# adp5350-breakout.net
KiCad netlist of a schematic drawn in EAGLE
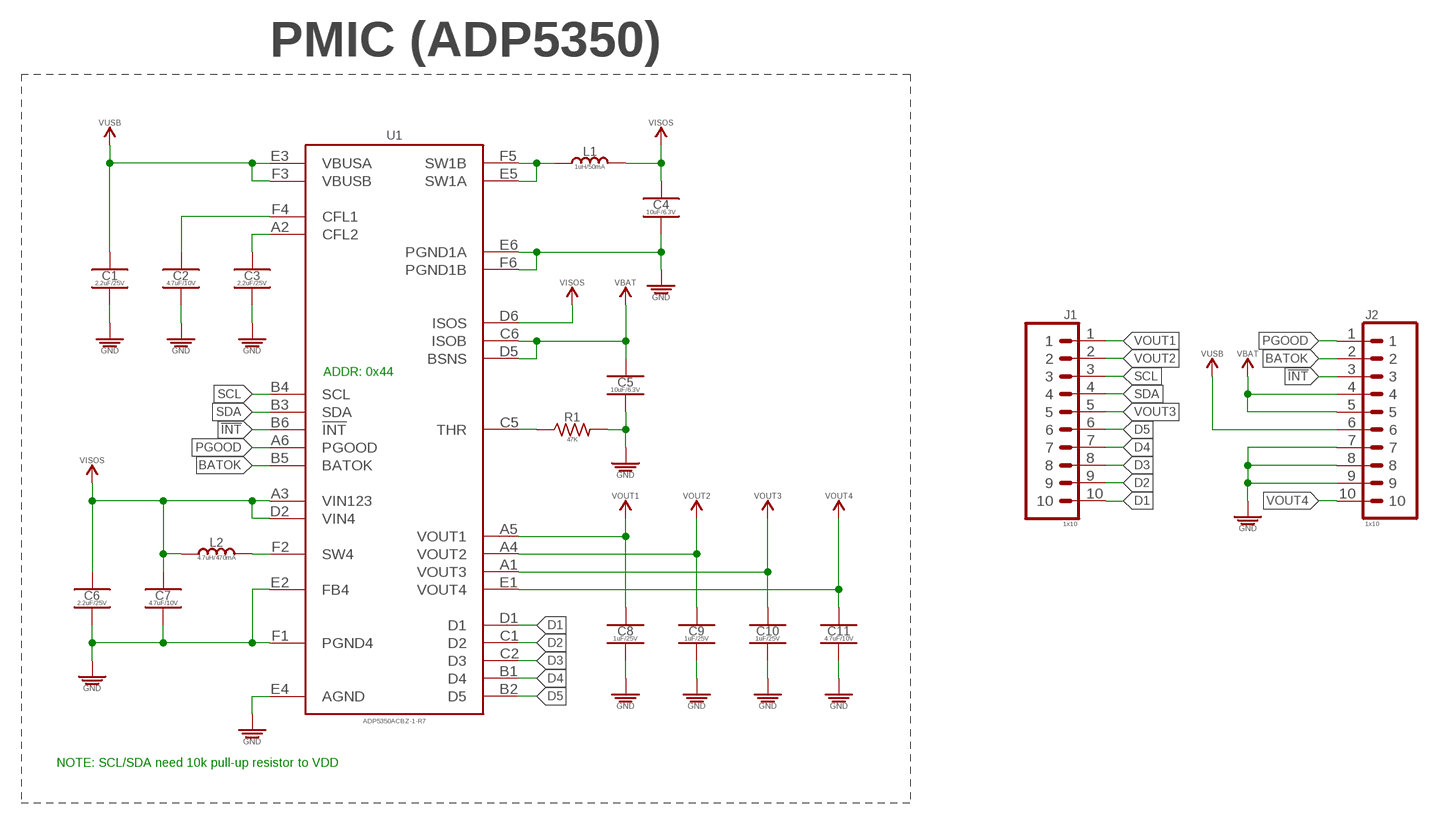
[diagram p0: schematic, sheet 1]

(export (version "E")
  (design (tool "Eeschema 10.0.6"))
  (components
    (comp (ref "C1")
      (value "2.2uF/25V")
      (footprint "eagle-import:CAPC1005X55_SMD-0402")
      (fields (field (name "MFR") "TDK Corporation") (field (name "MPN") "C1005X5R1E225K050BC"))
      (libsource (lib "eagle-import") (part "2.2UF_CER_SMD-0402_25V-10%"))
    )
    (comp (ref "C2")
      (value "4.7uF/10V")
      (footprint "eagle-import:CAPC1005X55_SMD-0402")
      (fields (field (name "MFR") "Samsung Electro-Mechanics") (field (name "MPN") "CL05A475MP5NRNC"))
      (libsource (lib "eagle-import") (part "4.7UF_CER_SMD-0402_10V-20%"))
    )
    (comp (ref "C3")
      (value "2.2uF/25V")
      (footprint "eagle-import:CAPC1005X55_SMD-0402")
      (fields (field (name "MFR") "TDK Corporation") (field (name "MPN") "C1005X5R1E225K050BC"))
      (libsource (lib "eagle-import") (part "2.2UF_CER_SMD-0402_25V-10%"))
    )
    (comp (ref "C4")
      (value "10uF/6.3V")
      (footprint "eagle-import:CAPC1005X55_SMD-0402")
      (fields
        (field (name "MFR") "Murata Electronics North America")
        (field (name "MPN") "GRM155C80J106ME11D")
      )
      (libsource (lib "eagle-import") (part "10UF_CER_SMD-0402_6.3V-20%"))
    )
    (comp (ref "C5")
      (value "10uF/6.3V")
      (footprint "eagle-import:CAPC1005X55_SMD-0402")
      (fields
        (field (name "MFR") "Murata Electronics North America")
        (field (name "MPN") "GRM155C80J106ME11D")
      )
      (libsource (lib "eagle-import") (part "10UF_CER_SMD-0402_6.3V-20%"))
    )
    (comp (ref "C6")
      (value "2.2uF/25V")
      (footprint "eagle-import:CAPC1005X55_SMD-0402")
      (fields (field (name "MFR") "TDK Corporation") (field (name "MPN") "C1005X5R1E225K050BC"))
      (libsource (lib "eagle-import") (part "2.2UF_CER_SMD-0402_25V-10%"))
    )
    (comp (ref "C7")
      (value "4.7uF/10V")
      (footprint "eagle-import:CAPC1005X55_SMD-0402")
      (fields (field (name "MFR") "Samsung Electro-Mechanics") (field (name "MPN") "CL05A475MP5NRNC"))
      (libsource (lib "eagle-import") (part "4.7UF_CER_SMD-0402_10V-20%"))
    )
    (comp (ref "C8")
      (value "1uF/25V")
      (footprint "eagle-import:CAPC1005X55_SMD-0402")
      (fields (field (name "MFR") "TDK Corporation") (field (name "MPN") "CGB2A1X5R1E105K033BC"))
      (libsource (lib "eagle-import") (part "1UF_CER_SMD-0402_25V-10%"))
    )
    (comp (ref "C9")
      (value "1uF/25V")
      (footprint "eagle-import:CAPC1005X55_SMD-0402")
      (fields (field (name "MFR") "TDK Corporation") (field (name "MPN") "CGB2A1X5R1E105K033BC"))
      (libsource (lib "eagle-import") (part "1UF_CER_SMD-0402_25V-10%"))
    )
    (comp (ref "C10")
      (value "1uF/25V")
      (footprint "eagle-import:CAPC1005X55_SMD-0402")
      (fields (field (name "MFR") "TDK Corporation") (field (name "MPN") "CGB2A1X5R1E105K033BC"))
      (libsource (lib "eagle-import") (part "1UF_CER_SMD-0402_25V-10%"))
    )
    (comp (ref "C11")
      (value "4.7uF/10V")
      (footprint "eagle-import:CAPC1005X55_SMD-0402")
      (fields (field (name "MFR") "Samsung Electro-Mechanics") (field (name "MPN") "CL05A475MP5NRNC"))
      (libsource (lib "eagle-import") (part "4.7UF_CER_SMD-0402_10V-20%"))
    )
    (comp (ref "J1")
      (value "1x10")
      (footprint "eagle-import:HDRV10W64P254_1X10_2540X254X838B")
      (fields (field (name "MFR") "Sullins Connector Solutions") (field (name "MPN") "PEC10SAAN"))
      (libsource (lib "eagle-import") (part "1X10_PTH_VERT-MALE_2.54MM"))
    )
    (comp (ref "J2")
      (value "1x10")
      (footprint "eagle-import:HDRV10W64P254_1X10_2540X254X838B")
      (fields (field (name "MFR") "Sullins Connector Solutions") (field (name "MPN") "PEC10SAAN"))
      (libsource (lib "eagle-import") (part "1X10_PTH_VERT-MALE_2.54MM"))
    )
    (comp (ref "L1")
      (value "1uH/50mA")
      (footprint "eagle-import:INDC1608X60-0603")
      (fields (field (name "MFR") "TDK Corporation") (field (name "MPN") "MLF1608A1R5KTA00"))
      (libsource (lib "eagle-import") (part "1UH_SMD-0603_0.50A-0.700OHM-10%"))
    )
    (comp (ref "L2")
      (value "4.7uH/470mA")
      (footprint "eagle-import:INDC1608X60-0603")
      (fields (field (name "MFR") "Taiyo Yuden") (field (name "MPN") "CBMF1608T4R7M"))
      (libsource (lib "eagle-import") (part "4.7UH_SMD-0603_470MA-0.312OHM-20%"))
    )
    (comp (ref "R1")
      (value "47K")
      (footprint "eagle-import:RESC1005X35_SMD-0402")
      (fields (field (name "MFR") "Yageo") (field (name "MPN") "AC0402JR-0747KL"))
      (libsource (lib "eagle-import") (part "47KΩ_SMD-0402_1/16W-5%"))
    )
    (comp (ref "U1")
      (value "ADP5350ACBZ-1-R7")
      (footprint "eagle-import:BGA36C50P6X6_331X336X66N")
      (fields (field (name "MFR") "Analog Devices Inc."))
      (libsource (lib "eagle-import") (part "ADP5350ACBZ-1-R7"))
    )
  )
  (nets
    (net (code "1") (name "/~{INT}") (class "Default")
      (node (ref "J2") (pin "3") (pinfunction "3_3") (pintype "passive"))
      (node (ref "U1") (pin "B6") (pinfunction "~{INT}_B6") (pintype "bidirectional"))
    )
    (net (code "2") (name "BATOK") (class "Default")
      (node (ref "J2") (pin "2") (pinfunction "2_2") (pintype "passive"))
      (node (ref "U1") (pin "B5") (pinfunction "BATOK_B5") (pintype "bidirectional"))
    )
    (net (code "3") (name "D1") (class "Default")
      (node (ref "J1") (pin "10") (pinfunction "10_10") (pintype "passive"))
      (node (ref "U1") (pin "D1") (pinfunction "D1_D1") (pintype "bidirectional"))
    )
    (net (code "4") (name "D2") (class "Default")
      (node (ref "J1") (pin "9") (pinfunction "9_9") (pintype "passive"))
      (node (ref "U1") (pin "C1") (pinfunction "D2_C1") (pintype "bidirectional"))
    )
    (net (code "5") (name "D3") (class "Default")
      (node (ref "J1") (pin "8") (pinfunction "8_8") (pintype "passive"))
      (node (ref "U1") (pin "C2") (pinfunction "D3_C2") (pintype "bidirectional"))
    )
    (net (code "6") (name "D4") (class "Default")
      (node (ref "J1") (pin "7") (pinfunction "7_7") (pintype "passive"))
      (node (ref "U1") (pin "B1") (pinfunction "D4_B1") (pintype "bidirectional"))
    )
    (net (code "7") (name "D5") (class "Default")
      (node (ref "J1") (pin "6") (pinfunction "6_6") (pintype "passive"))
      (node (ref "U1") (pin "B2") (pinfunction "D5_B2") (pintype "bidirectional"))
    )
    (net (code "8") (name "GND") (class "Default")
      (node (ref "C1") (pin "2") (pinfunction "2_2") (pintype "passive"))
      (node (ref "C10") (pin "2") (pinfunction "2_2") (pintype "passive"))
      (node (ref "C11") (pin "2") (pinfunction "2_2") (pintype "passive"))
      (node (ref "C2") (pin "2") (pinfunction "2_2") (pintype "passive"))
      (node (ref "C3") (pin "2") (pinfunction "2_2") (pintype "passive"))
      (node (ref "C4") (pin "2") (pinfunction "2_2") (pintype "passive"))
      (node (ref "C5") (pin "2") (pinfunction "2_2") (pintype "passive"))
      (node (ref "C6") (pin "2") (pinfunction "2_2") (pintype "passive"))
      (node (ref "C7") (pin "2") (pinfunction "2_2") (pintype "passive"))
      (node (ref "C8") (pin "2") (pinfunction "2_2") (pintype "passive"))
      (node (ref "C9") (pin "2") (pinfunction "2_2") (pintype "passive"))
      (node (ref "J2") (pin "7") (pinfunction "7_7") (pintype "passive"))
      (node (ref "J2") (pin "8") (pinfunction "8_8") (pintype "passive"))
      (node (ref "J2") (pin "9") (pinfunction "9_9") (pintype "passive"))
      (node (ref "R1") (pin "2") (pinfunction "2_2") (pintype "passive"))
      (node (ref "U1") (pin "E2") (pinfunction "FB4_E2") (pintype "bidirectional"))
      (node (ref "U1") (pin "E4") (pinfunction "AGND_E4") (pintype "power_in"))
      (node (ref "U1") (pin "E6") (pinfunction "PGND1A_E6") (pintype "power_in"))
      (node (ref "U1") (pin "F1") (pinfunction "PGND4_F1") (pintype "power_in"))
      (node (ref "U1") (pin "F6") (pinfunction "PGND1B_F6") (pintype "power_in"))
    )
    (net (code "9") (name "Net-(U1-CFL1)") (class "Default")
      (node (ref "C2") (pin "1") (pinfunction "1_1") (pintype "passive"))
      (node (ref "U1") (pin "F4") (pinfunction "CFL1_F4") (pintype "bidirectional"))
    )
    (net (code "10") (name "Net-(U1-CFL2)") (class "Default")
      (node (ref "C3") (pin "1") (pinfunction "1_1") (pintype "passive"))
      (node (ref "U1") (pin "A2") (pinfunction "CFL2_A2") (pintype "bidirectional"))
    )
    (net (code "11") (name "Net-(U1-SW1A)") (class "Default")
      (node (ref "L1") (pin "1") (pinfunction "1_1") (pintype "passive"))
      (node (ref "U1") (pin "E5") (pinfunction "SW1A_E5") (pintype "bidirectional"))
      (node (ref "U1") (pin "F5") (pinfunction "SW1B_F5") (pintype "bidirectional"))
    )
    (net (code "12") (name "Net-(U1-SW4)") (class "Default")
      (node (ref "L2") (pin "2") (pinfunction "2_2") (pintype "passive"))
      (node (ref "U1") (pin "F2") (pinfunction "SW4_F2") (pintype "bidirectional"))
    )
    (net (code "13") (name "Net-(U1-THR)") (class "Default")
      (node (ref "R1") (pin "1") (pinfunction "1_1") (pintype "passive"))
      (node (ref "U1") (pin "C5") (pinfunction "THR_C5") (pintype "bidirectional"))
    )
    (net (code "14") (name "PGOOD") (class "Default")
      (node (ref "J2") (pin "1") (pinfunction "1_1") (pintype "passive"))
      (node (ref "U1") (pin "A6") (pinfunction "PGOOD_A6") (pintype "bidirectional"))
    )
    (net (code "15") (name "SCL") (class "Default")
      (node (ref "J1") (pin "3") (pinfunction "3_3") (pintype "passive"))
      (node (ref "U1") (pin "B4") (pinfunction "SCL_B4") (pintype "bidirectional"))
    )
    (net (code "16") (name "SDA") (class "Default")
      (node (ref "J1") (pin "4") (pinfunction "4_4") (pintype "passive"))
      (node (ref "U1") (pin "B3") (pinfunction "SDA_B3") (pintype "bidirectional"))
    )
    (net (code "17") (name "VBAT") (class "Default")
      (node (ref "C5") (pin "1") (pinfunction "1_1") (pintype "passive"))
      (node (ref "J2") (pin "4") (pinfunction "4_4") (pintype "passive"))
      (node (ref "J2") (pin "5") (pinfunction "5_5") (pintype "passive"))
      (node (ref "U1") (pin "C6") (pinfunction "ISOB_C6") (pintype "bidirectional"))
      (node (ref "U1") (pin "D5") (pinfunction "BSNS_D5") (pintype "bidirectional"))
    )
    (net (code "18") (name "VISOS") (class "Default")
      (node (ref "C4") (pin "1") (pinfunction "1_1") (pintype "passive"))
      (node (ref "C6") (pin "1") (pinfunction "1_1") (pintype "passive"))
      (node (ref "C7") (pin "1") (pinfunction "1_1") (pintype "passive"))
      (node (ref "L1") (pin "2") (pinfunction "2_2") (pintype "passive"))
      (node (ref "L2") (pin "1") (pinfunction "1_1") (pintype "passive"))
      (node (ref "U1") (pin "A3") (pinfunction "VIN123_A3") (pintype "power_in"))
      (node (ref "U1") (pin "D2") (pinfunction "VIN4_D2") (pintype "power_in"))
      (node (ref "U1") (pin "D6") (pinfunction "ISOS_D6") (pintype "bidirectional"))
    )
    (net (code "19") (name "VOUT1") (class "Default")
      (node (ref "C8") (pin "1") (pinfunction "1_1") (pintype "passive"))
      (node (ref "J1") (pin "1") (pinfunction "1_1") (pintype "passive"))
      (node (ref "U1") (pin "A5") (pinfunction "VOUT1_A5") (pintype "power_in"))
    )
    (net (code "20") (name "VOUT2") (class "Default")
      (node (ref "C9") (pin "1") (pinfunction "1_1") (pintype "passive"))
      (node (ref "J1") (pin "2") (pinfunction "2_2") (pintype "passive"))
      (node (ref "U1") (pin "A4") (pinfunction "VOUT2_A4") (pintype "power_in"))
    )
    (net (code "21") (name "VOUT3") (class "Default")
      (node (ref "C10") (pin "1") (pinfunction "1_1") (pintype "passive"))
      (node (ref "J1") (pin "5") (pinfunction "5_5") (pintype "passive"))
      (node (ref "U1") (pin "A1") (pinfunction "VOUT3_A1") (pintype "power_in"))
    )
    (net (code "22") (name "VOUT4") (class "Default")
      (node (ref "C11") (pin "1") (pinfunction "1_1") (pintype "passive"))
      (node (ref "J2") (pin "10") (pinfunction "10_10") (pintype "passive"))
      (node (ref "U1") (pin "E1") (pinfunction "VOUT4_E1") (pintype "power_in"))
    )
    (net (code "23") (name "VUSB") (class "Default")
      (node (ref "C1") (pin "1") (pinfunction "1_1") (pintype "passive"))
      (node (ref "J2") (pin "6") (pinfunction "6_6") (pintype "passive"))
      (node (ref "U1") (pin "E3") (pinfunction "VBUSA_E3") (pintype "power_in"))
      (node (ref "U1") (pin "F3") (pinfunction "VBUSB_F3") (pintype "power_in"))
    )
  )
)
